# schematic.net
KiCad netlist of a schematic drawn in Altium Designer
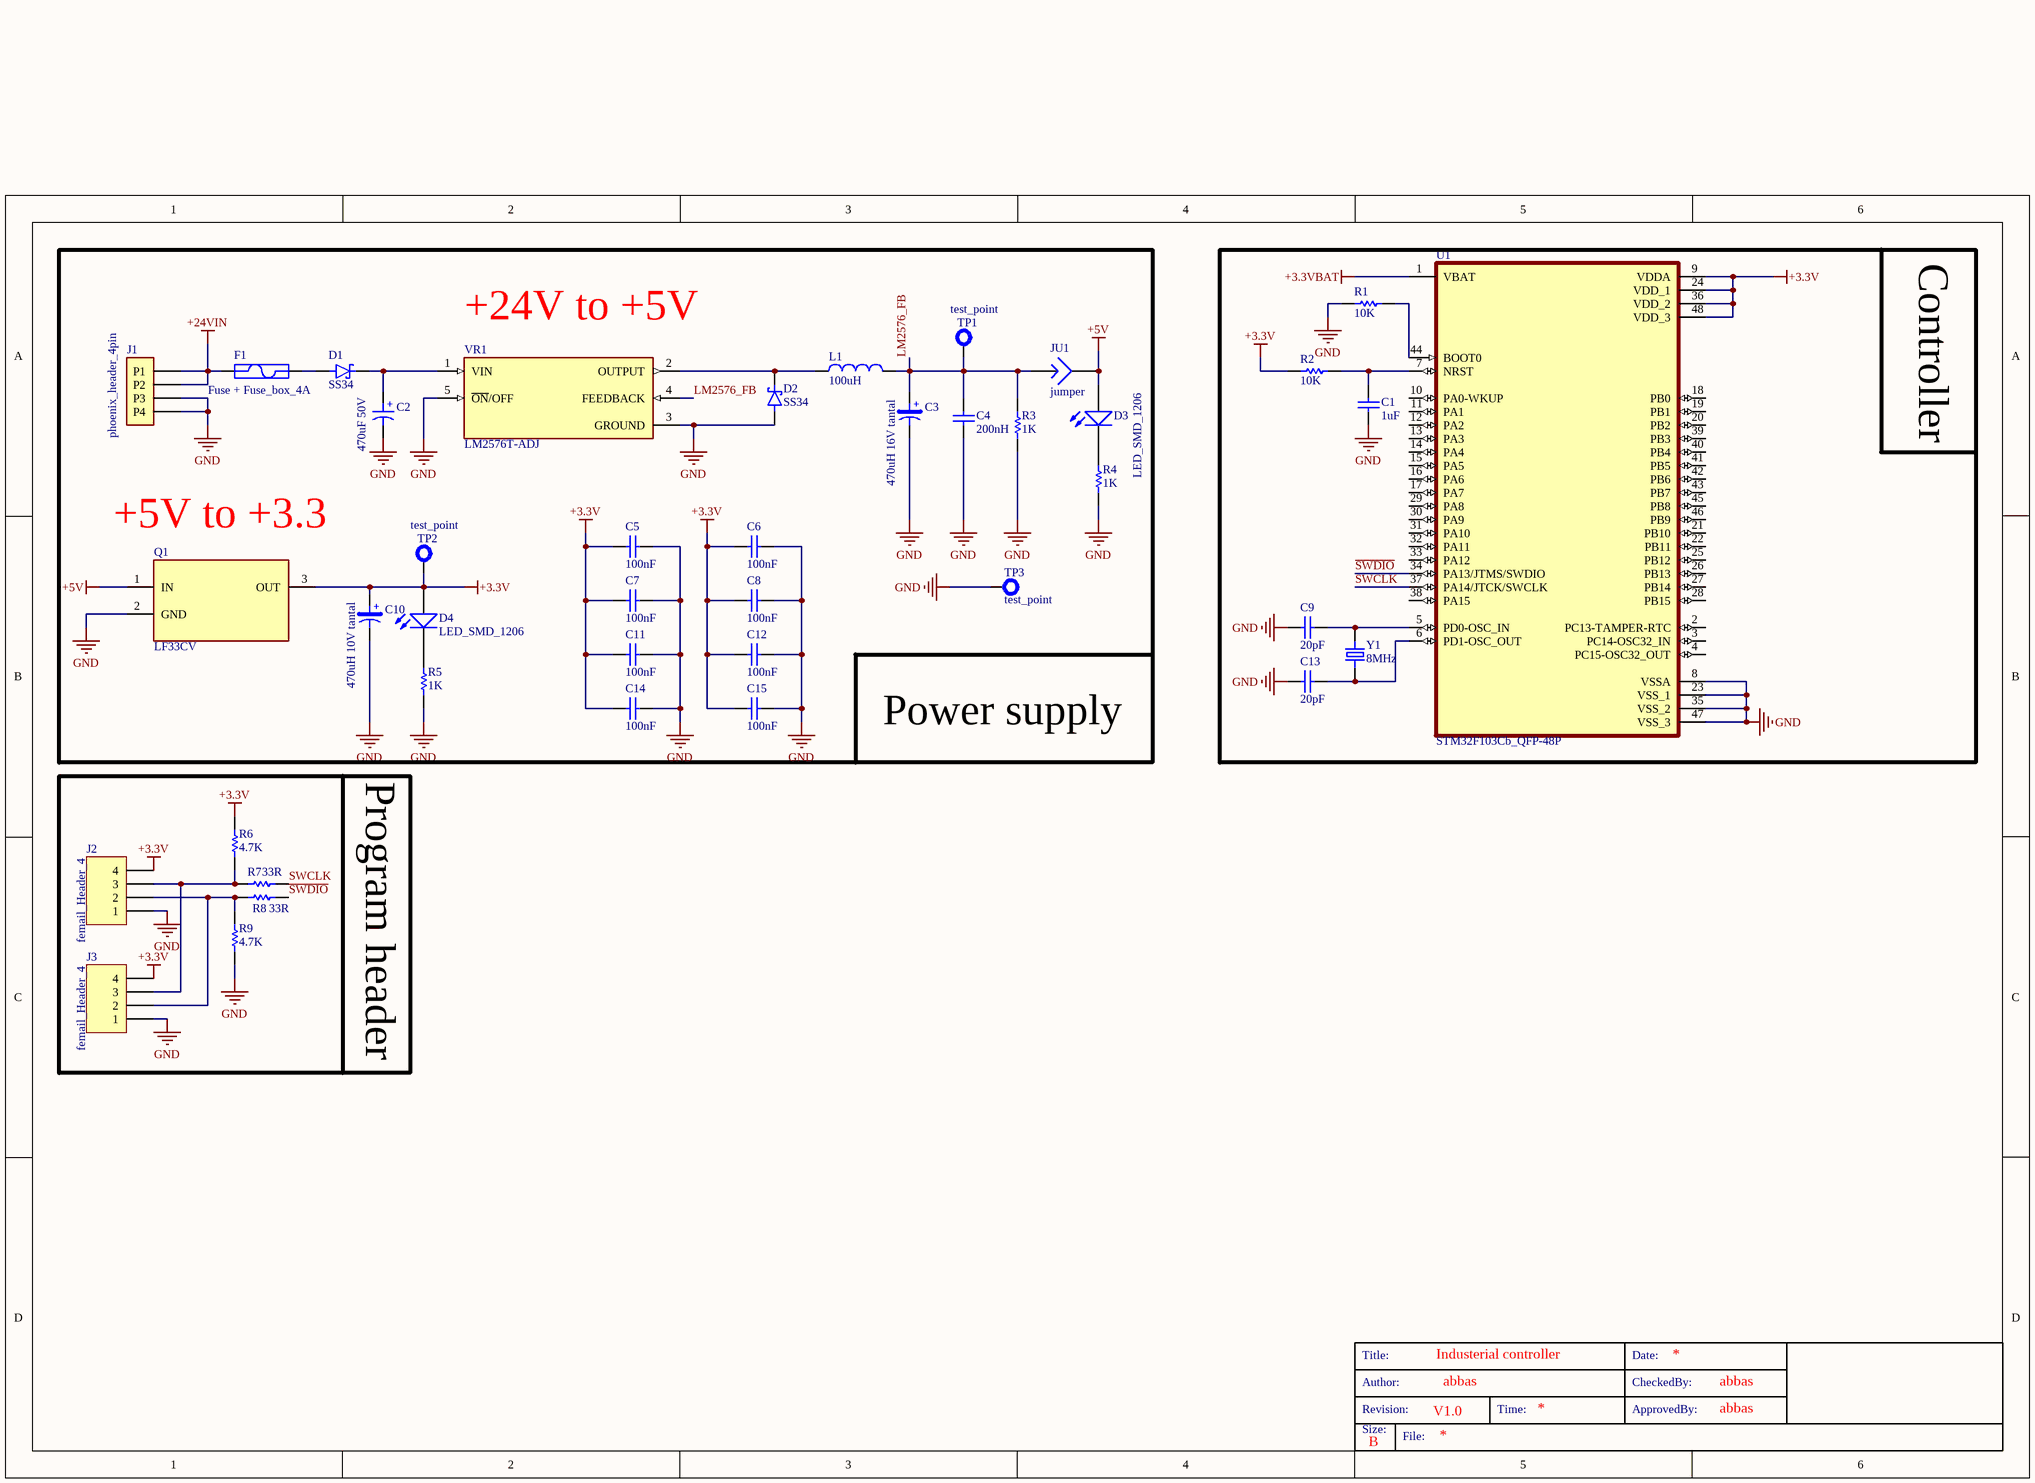
[diagram p0: schematic.SchDoc]

(export (version "E")
  (design (tool "Eeschema 10.0.6"))
  (components
    (comp (ref "C1")
      (value "1uF")
      (footprint "personal_library:cap ceramic 1206")
      (libsource (lib "personal_library") (part "cap ceramic 1206"))
    )
    (comp (ref "C2")
      (value "470uF 50V")
      (footprint "personal_library:capacity")
      (description "Cap electrolitic radial 6x7-2.5")
      (libsource (lib "personal_library") (part "Cap electrolitic radial 6x7-2.5"))
    )
    (comp (ref "C3")
      (value "470uH 16V tantal")
      (footprint "personal_library:Tantalium_cap_D size")
      (libsource (lib "personal_library") (part "tantalium_cap_D_size"))
    )
    (comp (ref "C4")
      (value "200nH")
      (footprint "personal_library:cap ceramic 1206")
      (libsource (lib "personal_library") (part "cap ceramic 1206"))
    )
    (comp (ref "C5")
      (value "100nF")
      (footprint "personal_library:cap ceramic 1206")
      (libsource (lib "personal_library") (part "cap ceramic 1206"))
    )
    (comp (ref "C6")
      (value "100nF")
      (footprint "personal_library:cap ceramic 1206")
      (libsource (lib "personal_library") (part "cap ceramic 1206"))
    )
    (comp (ref "C7")
      (value "100nF")
      (footprint "personal_library:cap ceramic 1206")
      (libsource (lib "personal_library") (part "cap ceramic 1206"))
    )
    (comp (ref "C8")
      (value "100nF")
      (footprint "personal_library:cap ceramic 1206")
      (libsource (lib "personal_library") (part "cap ceramic 1206"))
    )
    (comp (ref "C9")
      (value "20pF")
      (footprint "personal_library:cap ceramic 1206")
      (libsource (lib "personal_library") (part "cap ceramic 1206"))
    )
    (comp (ref "C10")
      (value "470uH 10V tantal")
      (footprint "personal_library:Tantalium_cap_D size")
      (libsource (lib "personal_library") (part "tantalium_cap_D_size"))
    )
    (comp (ref "C11")
      (value "100nF")
      (footprint "personal_library:cap ceramic 1206")
      (libsource (lib "personal_library") (part "cap ceramic 1206"))
    )
    (comp (ref "C12")
      (value "100nF")
      (footprint "personal_library:cap ceramic 1206")
      (libsource (lib "personal_library") (part "cap ceramic 1206"))
    )
    (comp (ref "C13")
      (value "20pF")
      (footprint "personal_library:cap ceramic 1206")
      (libsource (lib "personal_library") (part "cap ceramic 1206"))
    )
    (comp (ref "C14")
      (value "100nF")
      (footprint "personal_library:cap ceramic 1206")
      (libsource (lib "personal_library") (part "cap ceramic 1206"))
    )
    (comp (ref "C15")
      (value "100nF")
      (footprint "personal_library:cap ceramic 1206")
      (libsource (lib "personal_library") (part "cap ceramic 1206"))
    )
    (comp (ref "D1")
      (value "SS34")
      (footprint "personal_library:SS34_smd")
      (description "SMD schottky diode")
      (libsource (lib "personal_library") (part "SS34"))
    )
    (comp (ref "D2")
      (value "SS34")
      (footprint "personal_library:SS34_smd")
      (description "SMD schottky diode")
      (libsource (lib "personal_library") (part "SS34"))
    )
    (comp (ref "D3")
      (value "LED_SMD_1206")
      (footprint "personal_library:LED_SMD_1206")
      (libsource (lib "personal_library") (part "LED_SMD_1206"))
    )
    (comp (ref "D4")
      (value "LED_SMD_1206")
      (footprint "personal_library:LED_SMD_1206")
      (libsource (lib "personal_library") (part "LED_SMD_1206"))
    )
    (comp (ref "F1")
      (value "Fuse + Fuse_box_4A")
      (footprint "personal_library:Fuse_box")
      (libsource (lib "personal_library") (part "Fuse_box"))
    )
    (comp (ref "J1")
      (value "phoenix_header_4pin")
      (footprint "personal_library:phoenix_header_4pin")
      (description "Pluggable terminal block; socket; male; 3.5mm; angled 90Â°; ways: 4")
      (libsource (lib "personal_library") (part "phoenix_header_4pin"))
    )
    (comp (ref "J2")
      (value "femail_Header_4")
      (footprint "personal_library:femail_Header_4pin")
      (libsource (lib "personal_library") (part "Header_4pin"))
    )
    (comp (ref "J3")
      (value "femail_Header_4")
      (footprint "personal_library:femail_Header_4pin")
      (libsource (lib "personal_library") (part "Header_4pin"))
    )
    (comp (ref "JU1")
      (value "jumper")
      (footprint "personal_library:jumper")
      (libsource (lib "personal_library") (part "jumper"))
    )
    (comp (ref "L1")
      (value "100uH")
      (footprint "personal_library:Indicator_DIP")
      (libsource (lib "personal_library") (part "Indicator DIP"))
    )
    (comp (ref "Q1")
      (value "LF33CV")
      (footprint "personal_library:LF33CV_TO220_3")
      (description "Linear Voltage Regulator IC Positive Fixed 1 Output 500mA TO-220")
      (libsource (lib "personal_library") (part "LF33CV"))
    )
    (comp (ref "R1")
      (value "10K")
      (footprint "personal_library:resistor 1206")
      (libsource (lib "personal_library") (part "Resistor 1206"))
    )
    (comp (ref "R2")
      (value "10K")
      (footprint "personal_library:resistor 1206")
      (libsource (lib "personal_library") (part "Resistor 1206"))
    )
    (comp (ref "R3")
      (value "1K")
      (footprint "personal_library:resistor 1206")
      (libsource (lib "personal_library") (part "Resistor 1206"))
    )
    (comp (ref "R4")
      (value "1K")
      (footprint "personal_library:resistor 1206")
      (libsource (lib "personal_library") (part "Resistor 1206"))
    )
    (comp (ref "R5")
      (value "1K")
      (footprint "personal_library:resistor 1206")
      (libsource (lib "personal_library") (part "Resistor 1206"))
    )
    (comp (ref "R6")
      (value "4.7K")
      (footprint "personal_library:resistor 1206")
      (libsource (lib "personal_library") (part "Resistor 1206"))
    )
    (comp (ref "R7")
      (value "33R")
      (footprint "personal_library:resistor 1206")
      (libsource (lib "personal_library") (part "Resistor 1206"))
    )
    (comp (ref "R8")
      (value "33R")
      (footprint "personal_library:resistor 1206")
      (libsource (lib "personal_library") (part "Resistor 1206"))
    )
    (comp (ref "R9")
      (value "4.7K")
      (footprint "personal_library:resistor 1206")
      (libsource (lib "personal_library") (part "Resistor 1206"))
    )
    (comp (ref "TP1")
      (value "test_point")
      (footprint "personal_library:test_point")
      (libsource (lib "personal_library") (part "test_point"))
    )
    (comp (ref "TP2")
      (value "test_point")
      (footprint "personal_library:test_point")
      (libsource (lib "personal_library") (part "test_point"))
    )
    (comp (ref "TP3")
      (value "test_point")
      (footprint "personal_library:test_point")
      (libsource (lib "personal_library") (part "test_point"))
    )
    (comp (ref "U1")
      (value "STM32F103Cb_QFP-48P")
      (footprint "STM32F103Cb_QFP-48P")
      (description "ARMÂ® CortexÂ®-M3 STM32F1 Microcontroller IC 32-Bit Single-Core 72MHz 128KB (128K x 8) FLASH")
      (libsource (lib "personal_library") (part "STM32F103Cb_QFP-48P"))
    )
    (comp (ref "VR1")
      (value "LM2576T-ADJ")
      (footprint "personal_library:LM2576T-ADJ_TO220")
      (libsource (lib "personal_library") (part "LM2576T-ADJ"))
    )
    (comp (ref "Y1")
      (value "8MHz")
      (footprint "personal_library:Crystal_HC-49US")
      (libsource (lib "personal_library") (part "Crystal_HC-49US"))
    )
  )
  (nets
    (net (code "1") (name "+3.3V") (class "Default")
      (node (ref "C10") (pin "1") (pinfunction "1_1") (pintype "passive"))
      (node (ref "C11") (pin "2") (pinfunction "2_2") (pintype "passive"))
      (node (ref "C12") (pin "2") (pinfunction "2_2") (pintype "passive"))
      (node (ref "C14") (pin "2") (pinfunction "2_2") (pintype "passive"))
      (node (ref "C15") (pin "2") (pinfunction "2_2") (pintype "passive"))
      (node (ref "C5") (pin "2") (pinfunction "2_2") (pintype "passive"))
      (node (ref "C6") (pin "2") (pinfunction "2_2") (pintype "passive"))
      (node (ref "C7") (pin "2") (pinfunction "2_2") (pintype "passive"))
      (node (ref "C8") (pin "2") (pinfunction "2_2") (pintype "passive"))
      (node (ref "D4") (pin "2") (pinfunction "A_2") (pintype "passive"))
      (node (ref "J2") (pin "4") (pinfunction "4_4") (pintype "passive"))
      (node (ref "J3") (pin "4") (pinfunction "4_4") (pintype "passive"))
      (node (ref "Q1") (pin "3") (pinfunction "OUT_3") (pintype "power_in"))
      (node (ref "R2") (pin "2") (pinfunction "2_2") (pintype "passive"))
      (node (ref "R6") (pin "1") (pinfunction "1_1") (pintype "passive"))
      (node (ref "TP2") (pin "1") (pintype "passive"))
      (node (ref "U1") (pin "24") (pinfunction "VDD_1_24") (pintype "power_in"))
      (node (ref "U1") (pin "36") (pinfunction "VDD_2_36") (pintype "power_in"))
      (node (ref "U1") (pin "48") (pinfunction "VDD_3_48") (pintype "power_in"))
      (node (ref "U1") (pin "9") (pinfunction "VDDA_9") (pintype "power_in"))
    )
    (net (code "2") (name "+3.3VBAT") (class "Default")
      (node (ref "U1") (pin "1") (pinfunction "VBAT_1") (pintype "power_in"))
    )
    (net (code "3") (name "+5V") (class "Default")
      (node (ref "D3") (pin "2") (pinfunction "A_2") (pintype "passive"))
      (node (ref "JU1") (pin "2") (pinfunction "2_2") (pintype "passive"))
      (node (ref "Q1") (pin "1") (pinfunction "IN_1") (pintype "power_in"))
    )
    (net (code "4") (name "+24VIN") (class "Default")
      (node (ref "F1") (pin "1") (pinfunction "1_1") (pintype "passive"))
      (node (ref "J1") (pin "P1") (pinfunction "P1_P1") (pintype "power_in"))
      (node (ref "J1") (pin "P2") (pinfunction "P2_P2") (pintype "power_in"))
    )
    (net (code "5") (name "/LM2576_FB") (class "Default")
      (node (ref "C3") (pin "1") (pinfunction "1_1") (pintype "passive"))
      (node (ref "C4") (pin "2") (pinfunction "2_2") (pintype "passive"))
      (node (ref "JU1") (pin "1") (pinfunction "1_1") (pintype "passive"))
      (node (ref "L1") (pin "2") (pinfunction "2_2") (pintype "passive"))
      (node (ref "R3") (pin "2") (pinfunction "2_2") (pintype "passive"))
      (node (ref "TP1") (pin "1") (pintype "passive"))
      (node (ref "VR1") (pin "4") (pinfunction "FEEDBACK_4") (pintype "input"))
    )
    (net (code "6") (name "/SWCLK") (class "Default")
      (node (ref "R7") (pin "2") (pinfunction "2_2") (pintype "passive"))
      (node (ref "U1") (pin "37") (pinfunction "PA14/JTCK/SWCLK_37") (pintype "bidirectional"))
    )
    (net (code "7") (name "/SWDIO") (class "Default")
      (node (ref "R8") (pin "1") (pinfunction "1_1") (pintype "passive"))
      (node (ref "U1") (pin "34") (pinfunction "PA13/JTMS/SWDIO_34") (pintype "bidirectional"))
    )
    (net (code "8") (name "GND") (class "Default")
      (node (ref "C1") (pin "2") (pinfunction "2_2") (pintype "passive"))
      (node (ref "C10") (pin "2") (pinfunction "2_2") (pintype "passive"))
      (node (ref "C11") (pin "1") (pinfunction "1_1") (pintype "passive"))
      (node (ref "C12") (pin "1") (pinfunction "1_1") (pintype "passive"))
      (node (ref "C13") (pin "1") (pinfunction "1_1") (pintype "passive"))
      (node (ref "C14") (pin "1") (pinfunction "1_1") (pintype "passive"))
      (node (ref "C15") (pin "1") (pinfunction "1_1") (pintype "passive"))
      (node (ref "C2") (pin "2") (pinfunction "2_2") (pintype "passive"))
      (node (ref "C3") (pin "2") (pinfunction "2_2") (pintype "passive"))
      (node (ref "C4") (pin "1") (pinfunction "1_1") (pintype "passive"))
      (node (ref "C5") (pin "1") (pinfunction "1_1") (pintype "passive"))
      (node (ref "C6") (pin "1") (pinfunction "1_1") (pintype "passive"))
      (node (ref "C7") (pin "1") (pinfunction "1_1") (pintype "passive"))
      (node (ref "C8") (pin "1") (pinfunction "1_1") (pintype "passive"))
      (node (ref "C9") (pin "1") (pinfunction "1_1") (pintype "passive"))
      (node (ref "D2") (pin "A") (pinfunction "A_A") (pintype "passive"))
      (node (ref "J1") (pin "P3") (pinfunction "P3_P3") (pintype "power_in"))
      (node (ref "J1") (pin "P4") (pinfunction "P4_P4") (pintype "power_in"))
      (node (ref "J2") (pin "1") (pinfunction "1_1") (pintype "passive"))
      (node (ref "J3") (pin "1") (pinfunction "1_1") (pintype "passive"))
      (node (ref "Q1") (pin "2") (pinfunction "GND_2") (pintype "passive"))
      (node (ref "R1") (pin "2") (pinfunction "2_2") (pintype "passive"))
      (node (ref "R3") (pin "1") (pinfunction "1_1") (pintype "passive"))
      (node (ref "R4") (pin "1") (pinfunction "1_1") (pintype "passive"))
      (node (ref "R5") (pin "1") (pinfunction "1_1") (pintype "passive"))
      (node (ref "R9") (pin "2") (pinfunction "2_2") (pintype "passive"))
      (node (ref "TP3") (pin "1") (pintype "passive"))
      (node (ref "U1") (pin "23") (pinfunction "VSS_1_23") (pintype "power_in"))
      (node (ref "U1") (pin "35") (pinfunction "VSS_2_35") (pintype "power_in"))
      (node (ref "U1") (pin "47") (pinfunction "VSS_3_47") (pintype "power_in"))
      (node (ref "U1") (pin "8") (pinfunction "VSSA_8") (pintype "power_in"))
      (node (ref "VR1") (pin "3") (pinfunction "GROUND_3") (pintype "power_in"))
      (node (ref "VR1") (pin "5") (pinfunction "~{ON}/OFF_5") (pintype "input"))
    )
    (net (code "9") (name "Net-(D1-K)") (class "Default")
      (node (ref "C2") (pin "1") (pinfunction "1_1") (pintype "passive"))
      (node (ref "D1") (pin "C") (pinfunction "K_C") (pintype "passive"))
      (node (ref "VR1") (pin "1") (pinfunction "VIN_1") (pintype "input"))
    )
    (net (code "10") (name "Net-(D1-PadA)") (class "Default")
      (node (ref "D1") (pin "A") (pinfunction "A_A") (pintype "passive"))
      (node (ref "F1") (pin "2") (pinfunction "2_2") (pintype "passive"))
    )
    (net (code "11") (name "Net-(D2-K)") (class "Default")
      (node (ref "D2") (pin "C") (pinfunction "K_C") (pintype "passive"))
      (node (ref "L1") (pin "1") (pinfunction "1_1") (pintype "passive"))
      (node (ref "VR1") (pin "2") (pinfunction "OUTPUT_2") (pintype "output"))
    )
    (net (code "12") (name "Net-(D3-K)") (class "Default")
      (node (ref "D3") (pin "1") (pinfunction "K_1") (pintype "passive"))
      (node (ref "R4") (pin "2") (pinfunction "2_2") (pintype "passive"))
    )
    (net (code "13") (name "Net-(D4-K)") (class "Default")
      (node (ref "D4") (pin "1") (pinfunction "K_1") (pintype "passive"))
      (node (ref "R5") (pin "2") (pinfunction "2_2") (pintype "passive"))
    )
    (net (code "14") (name "Net-(J2-Pad2)") (class "Default")
      (node (ref "J2") (pin "2") (pinfunction "2_2") (pintype "passive"))
      (node (ref "J3") (pin "2") (pinfunction "2_2") (pintype "passive"))
      (node (ref "R8") (pin "2") (pinfunction "2_2") (pintype "passive"))
      (node (ref "R9") (pin "1") (pinfunction "1_1") (pintype "passive"))
    )
    (net (code "15") (name "Net-(J2-Pad3)") (class "Default")
      (node (ref "J2") (pin "3") (pinfunction "3_3") (pintype "passive"))
      (node (ref "J3") (pin "3") (pinfunction "3_3") (pintype "passive"))
      (node (ref "R6") (pin "2") (pinfunction "2_2") (pintype "passive"))
      (node (ref "R7") (pin "1") (pinfunction "1_1") (pintype "passive"))
    )
    (net (code "16") (name "Net-(U1-BOOT0)") (class "Default")
      (node (ref "R1") (pin "1") (pinfunction "1_1") (pintype "passive"))
      (node (ref "U1") (pin "44") (pinfunction "BOOT0_44") (pintype "input"))
    )
    (net (code "17") (name "Net-(U1-NRST)") (class "Default")
      (node (ref "C1") (pin "1") (pinfunction "1_1") (pintype "passive"))
      (node (ref "R2") (pin "1") (pinfunction "1_1") (pintype "passive"))
      (node (ref "U1") (pin "7") (pinfunction "NRST_7") (pintype "bidirectional"))
    )
    (net (code "18") (name "Net-(U1-PD0-OSC_IN)") (class "Default")
      (node (ref "C9") (pin "2") (pinfunction "2_2") (pintype "passive"))
      (node (ref "U1") (pin "5") (pinfunction "PD0-OSC_IN_5") (pintype "bidirectional"))
      (node (ref "Y1") (pin "1") (pinfunction "1_1") (pintype "passive"))
    )
    (net (code "19") (name "Net-(U1-PD1-OSC_OUT)") (class "Default")
      (node (ref "C13") (pin "2") (pinfunction "2_2") (pintype "passive"))
      (node (ref "U1") (pin "6") (pinfunction "PD1-OSC_OUT_6") (pintype "bidirectional"))
      (node (ref "Y1") (pin "2") (pinfunction "2_2") (pintype "passive"))
    )
    (net (code "20") (name "unconnected-(U1-PA0-WKUP-Pad10)") (class "Default")
      (node (ref "U1") (pin "10") (pinfunction "PA0-WKUP_10") (pintype "bidirectional"))
    )
    (net (code "21") (name "unconnected-(U1-PA1-Pad11)") (class "Default")
      (node (ref "U1") (pin "11") (pinfunction "PA1_11") (pintype "bidirectional"))
    )
    (net (code "22") (name "unconnected-(U1-PA2-Pad12)") (class "Default")
      (node (ref "U1") (pin "12") (pinfunction "PA2_12") (pintype "bidirectional"))
    )
    (net (code "23") (name "unconnected-(U1-PA3-Pad13)") (class "Default")
      (node (ref "U1") (pin "13") (pinfunction "PA3_13") (pintype "bidirectional"))
    )
    (net (code "24") (name "unconnected-(U1-PA4-Pad14)") (class "Default")
      (node (ref "U1") (pin "14") (pinfunction "PA4_14") (pintype "bidirectional"))
    )
    (net (code "25") (name "unconnected-(U1-PA5-Pad15)") (class "Default")
      (node (ref "U1") (pin "15") (pinfunction "PA5_15") (pintype "bidirectional"))
    )
    (net (code "26") (name "unconnected-(U1-PA6-Pad16)") (class "Default")
      (node (ref "U1") (pin "16") (pinfunction "PA6_16") (pintype "bidirectional"))
    )
    (net (code "27") (name "unconnected-(U1-PA7-Pad17)") (class "Default")
      (node (ref "U1") (pin "17") (pinfunction "PA7_17") (pintype "bidirectional"))
    )
    (net (code "28") (name "unconnected-(U1-PA8-Pad29)") (class "Default")
      (node (ref "U1") (pin "29") (pinfunction "PA8_29") (pintype "bidirectional"))
    )
    (net (code "29") (name "unconnected-(U1-PA9-Pad30)") (class "Default")
      (node (ref "U1") (pin "30") (pinfunction "PA9_30") (pintype "bidirectional"))
    )
    (net (code "30") (name "unconnected-(U1-PA10-Pad31)") (class "Default")
      (node (ref "U1") (pin "31") (pinfunction "PA10_31") (pintype "bidirectional"))
    )
    (net (code "31") (name "unconnected-(U1-PA11-Pad32)") (class "Default")
      (node (ref "U1") (pin "32") (pinfunction "PA11_32") (pintype "bidirectional"))
    )
    (net (code "32") (name "unconnected-(U1-PA12-Pad33)") (class "Default")
      (node (ref "U1") (pin "33") (pinfunction "PA12_33") (pintype "bidirectional"))
    )
    (net (code "33") (name "unconnected-(U1-PA15-Pad38)") (class "Default")
      (node (ref "U1") (pin "38") (pinfunction "PA15_38") (pintype "bidirectional"))
    )
    (net (code "34") (name "unconnected-(U1-PB0-Pad18)") (class "Default")
      (node (ref "U1") (pin "18") (pinfunction "PB0_18") (pintype "bidirectional"))
    )
    (net (code "35") (name "unconnected-(U1-PB1-Pad19)") (class "Default")
      (node (ref "U1") (pin "19") (pinfunction "PB1_19") (pintype "bidirectional"))
    )
    (net (code "36") (name "unconnected-(U1-PB2-Pad20)") (class "Default")
      (node (ref "U1") (pin "20") (pinfunction "PB2_20") (pintype "bidirectional"))
    )
    (net (code "37") (name "unconnected-(U1-PB3-Pad39)") (class "Default")
      (node (ref "U1") (pin "39") (pinfunction "PB3_39") (pintype "bidirectional"))
    )
    (net (code "38") (name "unconnected-(U1-PB4-Pad40)") (class "Default")
      (node (ref "U1") (pin "40") (pinfunction "PB4_40") (pintype "bidirectional"))
    )
    (net (code "39") (name "unconnected-(U1-PB5-Pad41)") (class "Default")
      (node (ref "U1") (pin "41") (pinfunction "PB5_41") (pintype "bidirectional"))
    )
    (net (code "40") (name "unconnected-(U1-PB6-Pad42)") (class "Default")
      (node (ref "U1") (pin "42") (pinfunction "PB6_42") (pintype "bidirectional"))
    )
    (net (code "41") (name "unconnected-(U1-PB7-Pad43)") (class "Default")
      (node (ref "U1") (pin "43") (pinfunction "PB7_43") (pintype "bidirectional"))
    )
    (net (code "42") (name "unconnected-(U1-PB8-Pad45)") (class "Default")
      (node (ref "U1") (pin "45") (pinfunction "PB8_45") (pintype "bidirectional"))
    )
    (net (code "43") (name "unconnected-(U1-PB9-Pad46)") (class "Default")
      (node (ref "U1") (pin "46") (pinfunction "PB9_46") (pintype "bidirectional"))
    )
    (net (code "44") (name "unconnected-(U1-PB10-Pad21)") (class "Default")
      (node (ref "U1") (pin "21") (pinfunction "PB10_21") (pintype "bidirectional"))
    )
    (net (code "45") (name "unconnected-(U1-PB11-Pad22)") (class "Default")
      (node (ref "U1") (pin "22") (pinfunction "PB11_22") (pintype "bidirectional"))
    )
    (net (code "46") (name "unconnected-(U1-PB12-Pad25)") (class "Default")
      (node (ref "U1") (pin "25") (pinfunction "PB12_25") (pintype "bidirectional"))
    )
    (net (code "47") (name "unconnected-(U1-PB13-Pad26)") (class "Default")
      (node (ref "U1") (pin "26") (pinfunction "PB13_26") (pintype "bidirectional"))
    )
    (net (code "48") (name "unconnected-(U1-PB14-Pad27)") (class "Default")
      (node (ref "U1") (pin "27") (pinfunction "PB14_27") (pintype "bidirectional"))
    )
    (net (code "49") (name "unconnected-(U1-PB15-Pad28)") (class "Default")
      (node (ref "U1") (pin "28") (pinfunction "PB15_28") (pintype "bidirectional"))
    )
    (net (code "50") (name "unconnected-(U1-PC13-TAMPER-RTC-Pad2)") (class "Default")
      (node (ref "U1") (pin "2") (pinfunction "PC13-TAMPER-RTC_2") (pintype "bidirectional"))
    )
    (net (code "51") (name "unconnected-(U1-PC14-OSC32_IN-Pad3)") (class "Default")
      (node (ref "U1") (pin "3") (pinfunction "PC14-OSC32_IN_3") (pintype "bidirectional"))
    )
    (net (code "52") (name "unconnected-(U1-PC15-OSC32_OUT-Pad4)") (class "Default")
      (node (ref "U1") (pin "4") (pinfunction "PC15-OSC32_OUT_4") (pintype "bidirectional"))
    )
  )
)
